# test.net
KiCad netlist of a schematic drawn in EAGLE
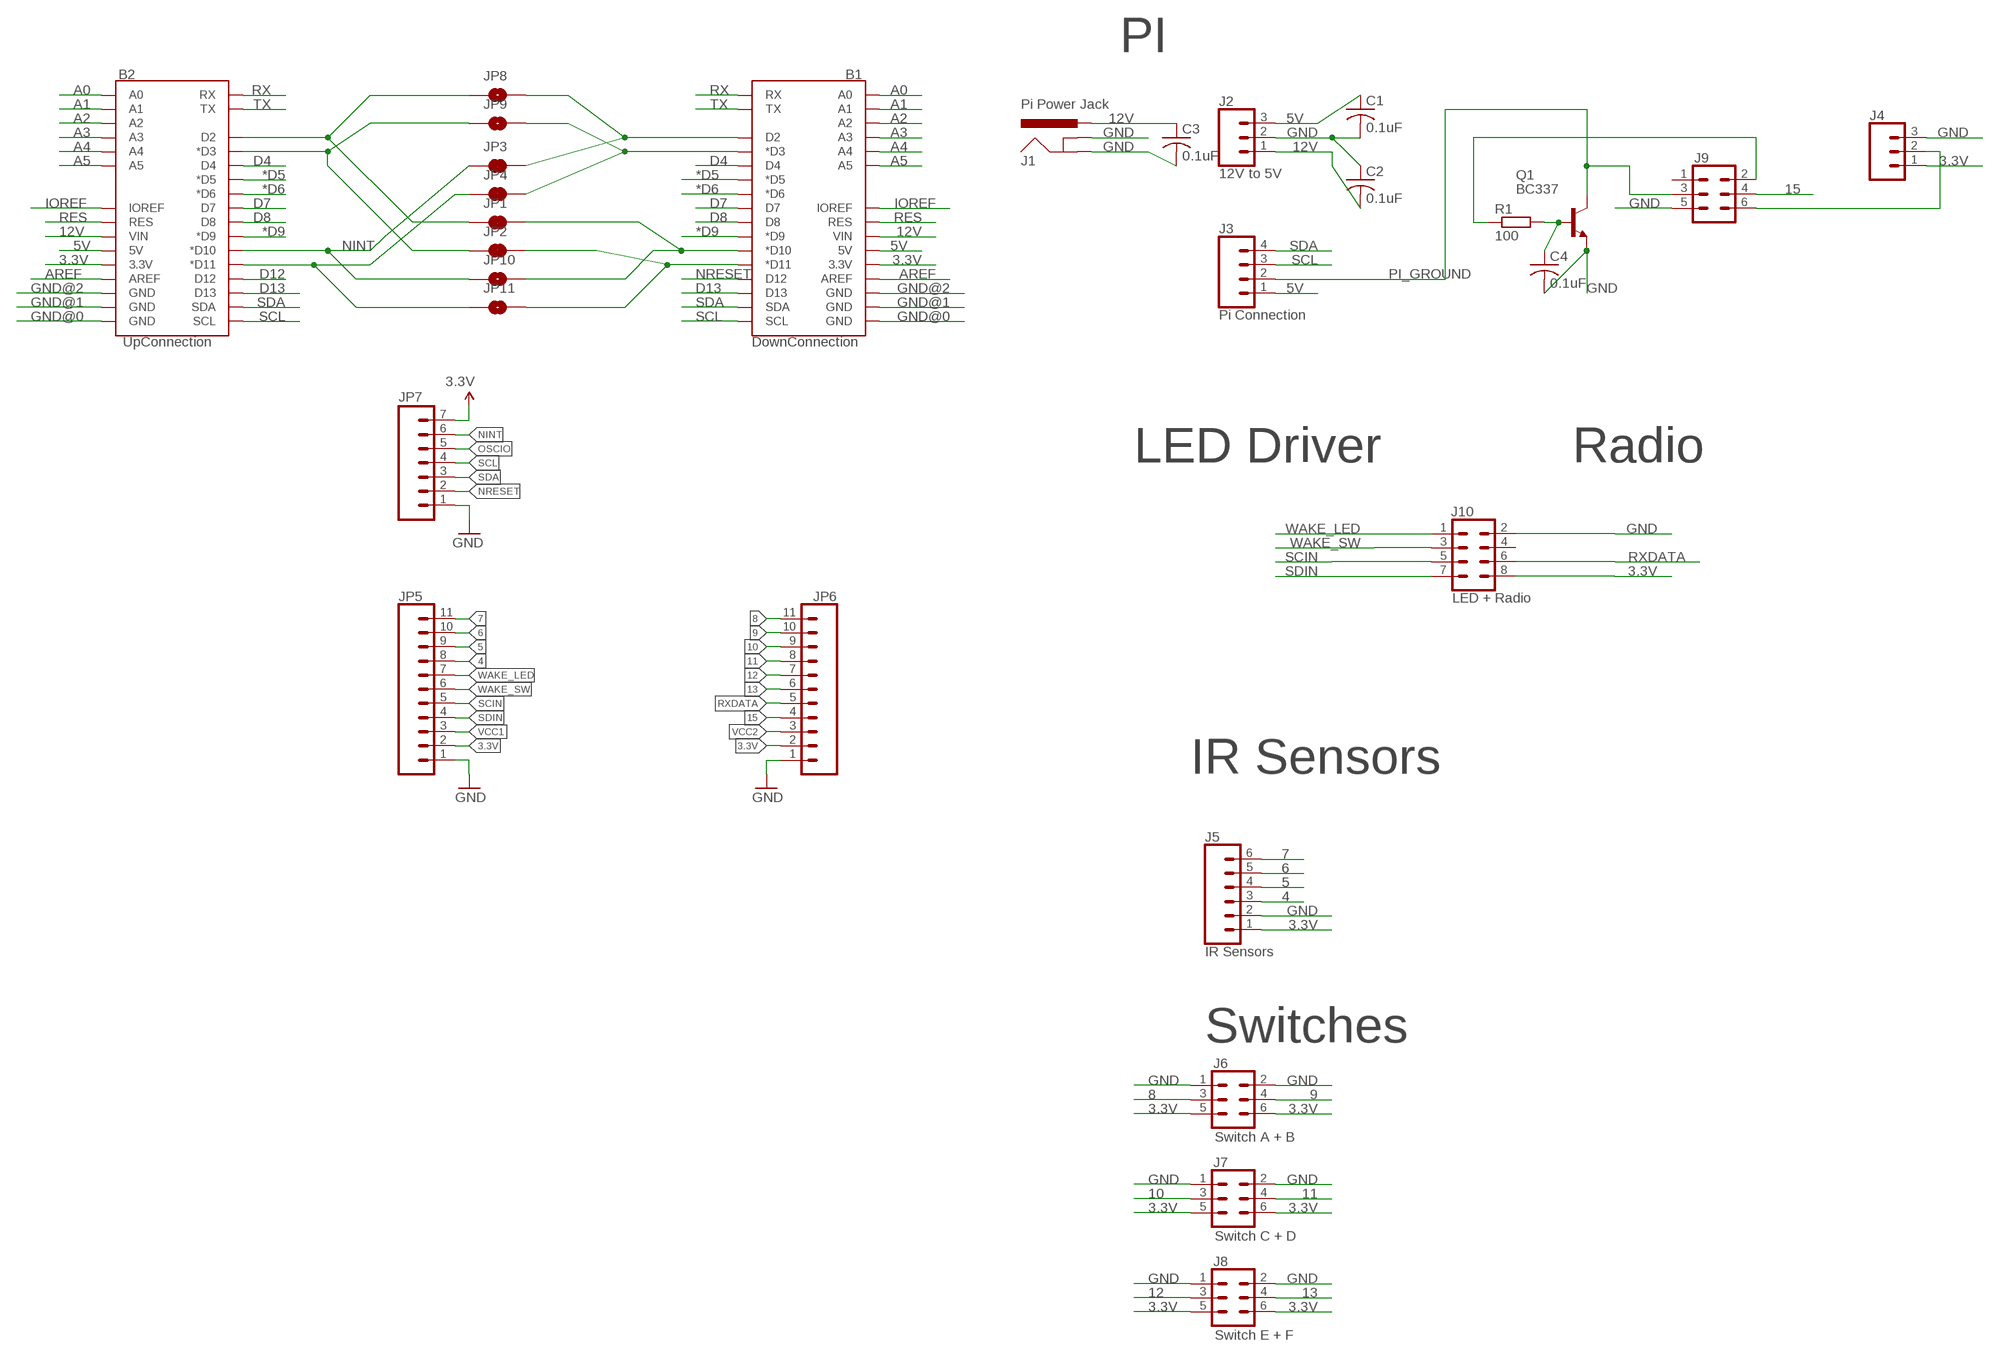
[diagram p0: schematic, sheet 1]

(export (version "E")
  (design (tool "Eeschema 10.0.6"))
  (components
    (comp (ref "B1")
      (value "DownConnection")
      (footprint "eagle-import:UNO_R3_SHIELD_NOLABELS")
      (libsource (lib "eagle-import") (part "ARDUINO_UNO_R3_SHIELDNOLABELS"))
    )
    (comp (ref "B2")
      (value "UpConnection")
      (footprint "eagle-import:UNO_R3_SHIELD_NOLABELS")
      (libsource (lib "eagle-import") (part "ARDUINO_UNO_R3_SHIELDNOLABELS"))
    )
    (comp (ref "C1")
      (value "0.1uF")
      (footprint "eagle-import:C025-024X044")
      (libsource (lib "eagle-import") (part "C-US025-024X044"))
    )
    (comp (ref "C2")
      (value "0.1uF")
      (footprint "eagle-import:C025-024X044")
      (libsource (lib "eagle-import") (part "C-US025-024X044"))
    )
    (comp (ref "C3")
      (value "0.1uF")
      (footprint "eagle-import:C025-024X044")
      (libsource (lib "eagle-import") (part "C-US025-024X044"))
    )
    (comp (ref "C4")
      (value "0.1uF")
      (footprint "eagle-import:C025-024X044")
      (libsource (lib "eagle-import") (part "C-US025-024X044"))
    )
    (comp (ref "J1")
      (value "Pi Power Jack")
      (footprint "eagle-import:POWER_JACK_PTH_BREAD")
      (libsource (lib "eagle-import") (part "POWER_JACKPTH_BREAD"))
    )
    (comp (ref "J2")
      (value "12V to 5V")
      (footprint "eagle-import:1X03")
      (libsource (lib "eagle-import") (part "CONN_03"))
    )
    (comp (ref "J3")
      (value "Pi Connection")
      (footprint "eagle-import:1X04")
      (libsource (lib "eagle-import") (part "CONN_04"))
    )
    (comp (ref "J4")
      (value "CONN_03")
      (footprint "eagle-import:1X03")
      (libsource (lib "eagle-import") (part "CONN_03"))
    )
    (comp (ref "J5")
      (value "IR Sensors")
      (footprint "eagle-import:1X06")
      (libsource (lib "eagle-import") (part "CONN_06SILK_FEMALE_PTH"))
    )
    (comp (ref "J6")
      (value "Switch A + B")
      (footprint "eagle-import:2X3")
      (libsource (lib "eagle-import") (part "CONN_03X2FEMALE"))
    )
    (comp (ref "J7")
      (value "Switch C + D")
      (footprint "eagle-import:2X3")
      (libsource (lib "eagle-import") (part "CONN_03X2FEMALE"))
    )
    (comp (ref "J8")
      (value "Switch E + F")
      (footprint "eagle-import:2X3")
      (libsource (lib "eagle-import") (part "CONN_03X2FEMALE"))
    )
    (comp (ref "J9")
      (value "CONN_03X2NO_SILK")
      (footprint "eagle-import:2X3-NS")
      (libsource (lib "eagle-import") (part "CONN_03X2NO_SILK"))
    )
    (comp (ref "J10")
      (value "LED + Radio")
      (footprint "eagle-import:2X4")
      (libsource (lib "eagle-import") (part "CONN_04X2"))
    )
    (comp (ref "JP1")
      (value "JUMPER-SMT_2_NC_TRACE_NO-SILK")
      (footprint "eagle-import:SMT-JUMPER_2_NC_TRACE_NO-SILK")
      (libsource (lib "eagle-import") (part "JUMPER-SMT_2_NC_TRACE_NO-SILK"))
    )
    (comp (ref "JP2")
      (value "JUMPER-SMT_2_NC_TRACE_NO-SILK")
      (footprint "eagle-import:SMT-JUMPER_2_NC_TRACE_NO-SILK")
      (libsource (lib "eagle-import") (part "JUMPER-SMT_2_NC_TRACE_NO-SILK"))
    )
    (comp (ref "JP3")
      (value "JUMPER-SMT_2_NC_TRACE_NO-SILK")
      (footprint "eagle-import:SMT-JUMPER_2_NC_TRACE_NO-SILK")
      (libsource (lib "eagle-import") (part "JUMPER-SMT_2_NC_TRACE_NO-SILK"))
    )
    (comp (ref "JP4")
      (value "JUMPER-SMT_2_NC_TRACE_NO-SILK")
      (footprint "eagle-import:SMT-JUMPER_2_NC_TRACE_NO-SILK")
      (libsource (lib "eagle-import") (part "JUMPER-SMT_2_NC_TRACE_NO-SILK"))
    )
    (comp (ref "JP5")
      (value "CONN_11")
      (footprint "eagle-import:1X11")
      (libsource (lib "eagle-import") (part "CONN_11"))
    )
    (comp (ref "JP6")
      (value "CONN_11")
      (footprint "eagle-import:1X11")
      (libsource (lib "eagle-import") (part "CONN_11"))
    )
    (comp (ref "JP7")
      (value "M07")
      (footprint "eagle-import:1X07")
      (libsource (lib "eagle-import") (part "M07"))
    )
    (comp (ref "JP8")
      (value "JUMPER-SMT_2_NO_NO-SILK")
      (footprint "eagle-import:SMT-JUMPER_2_NO_NO-SILK")
      (libsource (lib "eagle-import") (part "JUMPER-SMT_2_NO_NO-SILK"))
    )
    (comp (ref "JP9")
      (value "JUMPER-SMT_2_NO_NO-SILK")
      (footprint "eagle-import:SMT-JUMPER_2_NO_NO-SILK")
      (libsource (lib "eagle-import") (part "JUMPER-SMT_2_NO_NO-SILK"))
    )
    (comp (ref "JP10")
      (value "JUMPER-SMT_2_NO_NO-SILK")
      (footprint "eagle-import:SMT-JUMPER_2_NO_NO-SILK")
      (libsource (lib "eagle-import") (part "JUMPER-SMT_2_NO_NO-SILK"))
    )
    (comp (ref "JP11")
      (value "JUMPER-SMT_2_NO_NO-SILK")
      (footprint "eagle-import:SMT-JUMPER_2_NO_NO-SILK")
      (libsource (lib "eagle-import") (part "JUMPER-SMT_2_NO_NO-SILK"))
    )
    (comp (ref "Q1")
      (value "BC337")
      (footprint "eagle-import:TO92")
      (libsource (lib "eagle-import") (part "BC337"))
    )
    (comp (ref "R1")
      (value "100")
      (footprint "eagle-import:0204_7")
      (libsource (lib "eagle-import") (part "R0204/7"))
    )
  )
  (nets
    (net (code "1") (name "/*D5") (class "Default")
      (node (ref "B1") (pin "D5") (pinfunction "*D5_D5") (pintype "bidirectional"))
      (node (ref "B2") (pin "D5") (pinfunction "*D5_D5") (pintype "bidirectional"))
    )
    (net (code "2") (name "/*D6") (class "Default")
      (node (ref "B1") (pin "D6") (pinfunction "*D6_D6") (pintype "bidirectional"))
      (node (ref "B2") (pin "D6") (pinfunction "*D6_D6") (pintype "bidirectional"))
    )
    (net (code "3") (name "/*D9") (class "Default")
      (node (ref "B1") (pin "D9") (pinfunction "*D9_D9") (pintype "bidirectional"))
      (node (ref "B2") (pin "D9") (pinfunction "*D9_D9") (pintype "bidirectional"))
    )
    (net (code "4") (name "/5V") (class "Default")
      (node (ref "B1") (pin "5V") (pinfunction "5V_5V") (pintype "bidirectional"))
      (node (ref "B2") (pin "5V") (pinfunction "5V_5V") (pintype "bidirectional"))
      (node (ref "C1") (pin "1") (pinfunction "1_1") (pintype "passive"))
      (node (ref "J2") (pin "3") (pinfunction "3_3") (pintype "passive"))
      (node (ref "J3") (pin "1") (pinfunction "1_1") (pintype "passive"))
    )
    (net (code "5") (name "/12V") (class "Default")
      (node (ref "B1") (pin "VIN") (pinfunction "VIN_VIN") (pintype "bidirectional"))
      (node (ref "B2") (pin "VIN") (pinfunction "VIN_VIN") (pintype "bidirectional"))
      (node (ref "C2") (pin "2") (pinfunction "2_2") (pintype "passive"))
      (node (ref "C3") (pin "1") (pinfunction "1_1") (pintype "passive"))
      (node (ref "J1") (pin "PWR") (pinfunction "PWR_PWR") (pintype "bidirectional"))
      (node (ref "J2") (pin "1") (pinfunction "1_1") (pintype "passive"))
    )
    (net (code "6") (name "/A0") (class "Default")
      (node (ref "B1") (pin "A0") (pinfunction "A0_A0") (pintype "bidirectional"))
      (node (ref "B2") (pin "A0") (pinfunction "A0_A0") (pintype "bidirectional"))
    )
    (net (code "7") (name "/A1") (class "Default")
      (node (ref "B1") (pin "A1") (pinfunction "A1_A1") (pintype "bidirectional"))
      (node (ref "B2") (pin "A1") (pinfunction "A1_A1") (pintype "bidirectional"))
    )
    (net (code "8") (name "/A2") (class "Default")
      (node (ref "B1") (pin "A2") (pinfunction "A2_A2") (pintype "bidirectional"))
      (node (ref "B2") (pin "A2") (pinfunction "A2_A2") (pintype "bidirectional"))
    )
    (net (code "9") (name "/A3") (class "Default")
      (node (ref "B1") (pin "A3") (pinfunction "A3_A3") (pintype "bidirectional"))
      (node (ref "B2") (pin "A3") (pinfunction "A3_A3") (pintype "bidirectional"))
    )
    (net (code "10") (name "/A4") (class "Default")
      (node (ref "B1") (pin "A4") (pinfunction "A4_A4") (pintype "bidirectional"))
      (node (ref "B2") (pin "A4") (pinfunction "A4_A4") (pintype "bidirectional"))
    )
    (net (code "11") (name "/A5") (class "Default")
      (node (ref "B1") (pin "A5") (pinfunction "A5_A5") (pintype "bidirectional"))
      (node (ref "B2") (pin "A5") (pinfunction "A5_A5") (pintype "bidirectional"))
    )
    (net (code "12") (name "/AREF") (class "Default")
      (node (ref "B1") (pin "AREF") (pinfunction "AREF_AREF") (pintype "bidirectional"))
      (node (ref "B2") (pin "AREF") (pinfunction "AREF_AREF") (pintype "bidirectional"))
    )
    (net (code "13") (name "/D4") (class "Default")
      (node (ref "B1") (pin "D4") (pinfunction "D4_D4") (pintype "bidirectional"))
      (node (ref "B2") (pin "D4") (pinfunction "D4_D4") (pintype "bidirectional"))
    )
    (net (code "14") (name "/D7") (class "Default")
      (node (ref "B1") (pin "D7") (pinfunction "D7_D7") (pintype "bidirectional"))
      (node (ref "B2") (pin "D7") (pinfunction "D7_D7") (pintype "bidirectional"))
    )
    (net (code "15") (name "/D8") (class "Default")
      (node (ref "B1") (pin "D8") (pinfunction "D8_D8") (pintype "bidirectional"))
      (node (ref "B2") (pin "D8") (pinfunction "D8_D8") (pintype "bidirectional"))
    )
    (net (code "16") (name "/D12") (class "Default")
      (node (ref "B2") (pin "D12") (pinfunction "D12_D12") (pintype "bidirectional"))
    )
    (net (code "17") (name "/D13") (class "Default")
      (node (ref "B1") (pin "D13") (pinfunction "D13_D13") (pintype "bidirectional"))
      (node (ref "B2") (pin "D13") (pinfunction "D13_D13") (pintype "bidirectional"))
    )
    (net (code "18") (name "/GND@0") (class "Default")
      (node (ref "B1") (pin "GND@0") (pinfunction "GND_GND@0") (pintype "bidirectional"))
      (node (ref "B2") (pin "GND@0") (pinfunction "GND_GND@0") (pintype "bidirectional"))
    )
    (net (code "19") (name "/GND@1") (class "Default")
      (node (ref "B1") (pin "GND@1") (pinfunction "GND_GND@1") (pintype "bidirectional"))
      (node (ref "B2") (pin "GND@1") (pinfunction "GND_GND@1") (pintype "bidirectional"))
    )
    (net (code "20") (name "/GND@2") (class "Default")
      (node (ref "B1") (pin "GND@2") (pinfunction "GND_GND@2") (pintype "bidirectional"))
      (node (ref "B2") (pin "GND@2") (pinfunction "GND_GND@2") (pintype "bidirectional"))
    )
    (net (code "21") (name "/IOREF") (class "Default")
      (node (ref "B1") (pin "IOREF") (pinfunction "IOREF_IOREF") (pintype "bidirectional"))
      (node (ref "B2") (pin "IOREF") (pinfunction "IOREF_IOREF") (pintype "bidirectional"))
    )
    (net (code "22") (name "/PI_GROUND") (class "Default")
      (node (ref "J3") (pin "2") (pinfunction "2_2") (pintype "passive"))
      (node (ref "J9") (pin "3") (pinfunction "3_3") (pintype "bidirectional"))
      (node (ref "Q1") (pin "3") (pinfunction "C_3") (pintype "passive"))
    )
    (net (code "23") (name "/RES") (class "Default")
      (node (ref "B1") (pin "RES") (pinfunction "RES_RES") (pintype "bidirectional"))
      (node (ref "B2") (pin "RES") (pinfunction "RES_RES") (pintype "bidirectional"))
    )
    (net (code "24") (name "/RX") (class "Default")
      (node (ref "B1") (pin "RX") (pinfunction "RX_RX") (pintype "bidirectional"))
      (node (ref "B2") (pin "RX") (pinfunction "RX_RX") (pintype "bidirectional"))
    )
    (net (code "25") (name "/TX") (class "Default")
      (node (ref "B1") (pin "TX") (pinfunction "TX_TX") (pintype "bidirectional"))
      (node (ref "B2") (pin "TX") (pinfunction "TX_TX") (pintype "bidirectional"))
    )
    (net (code "26") (name "3.3V") (class "Default")
      (node (ref "B1") (pin "3.3V") (pinfunction "3.3V_3.3V") (pintype "bidirectional"))
      (node (ref "B2") (pin "3.3V") (pinfunction "3.3V_3.3V") (pintype "bidirectional"))
      (node (ref "J10") (pin "8") (pinfunction "8_8") (pintype "passive"))
      (node (ref "J4") (pin "1") (pinfunction "1_1") (pintype "passive"))
      (node (ref "J5") (pin "1") (pinfunction "1_1") (pintype "passive"))
      (node (ref "J6") (pin "5") (pinfunction "5_5") (pintype "bidirectional"))
      (node (ref "J6") (pin "6") (pinfunction "6_6") (pintype "bidirectional"))
      (node (ref "J7") (pin "5") (pinfunction "5_5") (pintype "bidirectional"))
      (node (ref "J7") (pin "6") (pinfunction "6_6") (pintype "bidirectional"))
      (node (ref "J8") (pin "5") (pinfunction "5_5") (pintype "bidirectional"))
      (node (ref "J8") (pin "6") (pinfunction "6_6") (pintype "bidirectional"))
      (node (ref "JP5") (pin "2") (pinfunction "2_2") (pintype "passive"))
      (node (ref "JP6") (pin "2") (pinfunction "2_2") (pintype "passive"))
      (node (ref "JP7") (pin "7") (pinfunction "7_7") (pintype "passive"))
    )
    (net (code "27") (name "4") (class "Default")
      (node (ref "J5") (pin "3") (pinfunction "3_3") (pintype "passive"))
      (node (ref "JP5") (pin "8") (pinfunction "8_8") (pintype "passive"))
    )
    (net (code "28") (name "5") (class "Default")
      (node (ref "J5") (pin "4") (pinfunction "4_4") (pintype "passive"))
      (node (ref "JP5") (pin "9") (pinfunction "9_9") (pintype "passive"))
    )
    (net (code "29") (name "6") (class "Default")
      (node (ref "J5") (pin "5") (pinfunction "5_5") (pintype "passive"))
      (node (ref "JP5") (pin "10") (pinfunction "10_10") (pintype "passive"))
    )
    (net (code "30") (name "7") (class "Default")
      (node (ref "J5") (pin "6") (pinfunction "6_6") (pintype "passive"))
      (node (ref "JP5") (pin "11") (pinfunction "11_11") (pintype "passive"))
    )
    (net (code "31") (name "8") (class "Default")
      (node (ref "J6") (pin "3") (pinfunction "3_3") (pintype "bidirectional"))
      (node (ref "JP6") (pin "11") (pinfunction "11_11") (pintype "passive"))
    )
    (net (code "32") (name "9") (class "Default")
      (node (ref "J6") (pin "4") (pinfunction "4_4") (pintype "bidirectional"))
      (node (ref "JP6") (pin "10") (pinfunction "10_10") (pintype "passive"))
    )
    (net (code "33") (name "10") (class "Default")
      (node (ref "J7") (pin "3") (pinfunction "3_3") (pintype "bidirectional"))
      (node (ref "JP6") (pin "9") (pinfunction "9_9") (pintype "passive"))
    )
    (net (code "34") (name "11") (class "Default")
      (node (ref "J7") (pin "4") (pinfunction "4_4") (pintype "bidirectional"))
      (node (ref "JP6") (pin "8") (pinfunction "8_8") (pintype "passive"))
    )
    (net (code "35") (name "12") (class "Default")
      (node (ref "J8") (pin "3") (pinfunction "3_3") (pintype "bidirectional"))
      (node (ref "JP6") (pin "7") (pinfunction "7_7") (pintype "passive"))
    )
    (net (code "36") (name "13") (class "Default")
      (node (ref "J8") (pin "4") (pinfunction "4_4") (pintype "bidirectional"))
      (node (ref "JP6") (pin "6") (pinfunction "6_6") (pintype "passive"))
    )
    (net (code "37") (name "15") (class "Default")
      (node (ref "J9") (pin "4") (pinfunction "4_4") (pintype "bidirectional"))
      (node (ref "JP6") (pin "4") (pinfunction "4_4") (pintype "passive"))
    )
    (net (code "38") (name "GND") (class "Default")
      (node (ref "C1") (pin "2") (pinfunction "2_2") (pintype "passive"))
      (node (ref "C2") (pin "1") (pinfunction "1_1") (pintype "passive"))
      (node (ref "C3") (pin "2") (pinfunction "2_2") (pintype "passive"))
      (node (ref "C4") (pin "2") (pinfunction "2_2") (pintype "passive"))
      (node (ref "J1") (pin "GND") (pinfunction "GND_GND") (pintype "bidirectional"))
      (node (ref "J1") (pin "GNDBREAK") (pinfunction "GNDBREAK_GNDBREAK") (pintype "bidirectional"))
      (node (ref "J10") (pin "2") (pinfunction "2_2") (pintype "passive"))
      (node (ref "J2") (pin "2") (pinfunction "2_2") (pintype "passive"))
      (node (ref "J4") (pin "3") (pinfunction "3_3") (pintype "passive"))
      (node (ref "J5") (pin "2") (pinfunction "2_2") (pintype "passive"))
      (node (ref "J6") (pin "1") (pinfunction "1_1") (pintype "bidirectional"))
      (node (ref "J6") (pin "2") (pinfunction "2_2") (pintype "bidirectional"))
      (node (ref "J7") (pin "1") (pinfunction "1_1") (pintype "bidirectional"))
      (node (ref "J7") (pin "2") (pinfunction "2_2") (pintype "bidirectional"))
      (node (ref "J8") (pin "1") (pinfunction "1_1") (pintype "bidirectional"))
      (node (ref "J8") (pin "2") (pinfunction "2_2") (pintype "bidirectional"))
      (node (ref "J9") (pin "5") (pinfunction "5_5") (pintype "bidirectional"))
      (node (ref "JP5") (pin "1") (pinfunction "1_1") (pintype "passive"))
      (node (ref "JP6") (pin "1") (pinfunction "1_1") (pintype "passive"))
      (node (ref "JP7") (pin "1") (pinfunction "1_1") (pintype "passive"))
      (node (ref "Q1") (pin "1") (pinfunction "E_1") (pintype "passive"))
    )
    (net (code "39") (name "NINT") (class "Default")
      (node (ref "B2") (pin "D10") (pinfunction "*D10_D10") (pintype "bidirectional"))
      (node (ref "JP10") (pin "1") (pinfunction "1_1") (pintype "passive"))
      (node (ref "JP3") (pin "1") (pinfunction "1_1") (pintype "passive"))
      (node (ref "JP7") (pin "6") (pinfunction "6_6") (pintype "passive"))
    )
    (net (code "40") (name "NRESET") (class "Default")
      (node (ref "B1") (pin "D12") (pinfunction "D12_D12") (pintype "bidirectional"))
      (node (ref "JP7") (pin "2") (pinfunction "2_2") (pintype "passive"))
    )
    (net (code "41") (name "Net-(B1-*D3)") (class "Default")
      (node (ref "B1") (pin "D3") (pinfunction "*D3_D3") (pintype "bidirectional"))
      (node (ref "JP4") (pin "2") (pinfunction "2_2") (pintype "passive"))
      (node (ref "JP9") (pin "2") (pinfunction "2_2") (pintype "passive"))
    )
    (net (code "42") (name "Net-(B1-*D10)") (class "Default")
      (node (ref "B1") (pin "D10") (pinfunction "*D10_D10") (pintype "bidirectional"))
      (node (ref "JP1") (pin "2") (pinfunction "2_2") (pintype "passive"))
      (node (ref "JP10") (pin "2") (pinfunction "2_2") (pintype "passive"))
    )
    (net (code "43") (name "Net-(B1-*D11)") (class "Default")
      (node (ref "B1") (pin "D11") (pinfunction "*D11_D11") (pintype "bidirectional"))
      (node (ref "JP11") (pin "2") (pinfunction "2_2") (pintype "passive"))
      (node (ref "JP2") (pin "2") (pinfunction "2_2") (pintype "passive"))
    )
    (net (code "44") (name "Net-(B1-PadD2)") (class "Default")
      (node (ref "B1") (pin "D2") (pinfunction "D2_D2") (pintype "bidirectional"))
      (node (ref "JP3") (pin "2") (pinfunction "2_2") (pintype "passive"))
      (node (ref "JP8") (pin "2") (pinfunction "2_2") (pintype "passive"))
    )
    (net (code "45") (name "Net-(B2-*D3)") (class "Default")
      (node (ref "B2") (pin "D3") (pinfunction "*D3_D3") (pintype "bidirectional"))
      (node (ref "JP2") (pin "1") (pinfunction "1_1") (pintype "passive"))
      (node (ref "JP9") (pin "1") (pinfunction "1_1") (pintype "passive"))
    )
    (net (code "46") (name "Net-(B2-*D11)") (class "Default")
      (node (ref "B2") (pin "D11") (pinfunction "*D11_D11") (pintype "bidirectional"))
      (node (ref "JP11") (pin "1") (pinfunction "1_1") (pintype "passive"))
      (node (ref "JP4") (pin "1") (pinfunction "1_1") (pintype "passive"))
    )
    (net (code "47") (name "Net-(B2-PadD2)") (class "Default")
      (node (ref "B2") (pin "D2") (pinfunction "D2_D2") (pintype "bidirectional"))
      (node (ref "JP1") (pin "1") (pinfunction "1_1") (pintype "passive"))
      (node (ref "JP8") (pin "1") (pinfunction "1_1") (pintype "passive"))
    )
    (net (code "48") (name "Net-(J4-Pad2)") (class "Default")
      (node (ref "J4") (pin "2") (pinfunction "2_2") (pintype "passive"))
      (node (ref "J9") (pin "6") (pinfunction "6_6") (pintype "bidirectional"))
    )
    (net (code "49") (name "Net-(J9-Pad2)") (class "Default")
      (node (ref "J9") (pin "2") (pinfunction "2_2") (pintype "bidirectional"))
      (node (ref "R1") (pin "1") (pinfunction "1_1") (pintype "passive"))
    )
    (net (code "50") (name "Net-(Q1-B)") (class "Default")
      (node (ref "C4") (pin "1") (pinfunction "1_1") (pintype "passive"))
      (node (ref "Q1") (pin "2") (pinfunction "B_2") (pintype "passive"))
      (node (ref "R1") (pin "2") (pinfunction "2_2") (pintype "passive"))
    )
    (net (code "51") (name "OSCIO") (class "Default")
      (node (ref "JP7") (pin "5") (pinfunction "5_5") (pintype "passive"))
    )
    (net (code "52") (name "RXDATA") (class "Default")
      (node (ref "J10") (pin "6") (pinfunction "6_6") (pintype "passive"))
      (node (ref "JP6") (pin "5") (pinfunction "5_5") (pintype "passive"))
    )
    (net (code "53") (name "SCIN") (class "Default")
      (node (ref "J10") (pin "5") (pinfunction "5_5") (pintype "passive"))
      (node (ref "JP5") (pin "5") (pinfunction "5_5") (pintype "passive"))
    )
    (net (code "54") (name "SCL") (class "Default")
      (node (ref "B1") (pin "SCL") (pinfunction "SCL_SCL") (pintype "bidirectional"))
      (node (ref "B2") (pin "SCL") (pinfunction "SCL_SCL") (pintype "bidirectional"))
      (node (ref "J3") (pin "3") (pinfunction "3_3") (pintype "passive"))
      (node (ref "JP7") (pin "4") (pinfunction "4_4") (pintype "passive"))
    )
    (net (code "55") (name "SDA") (class "Default")
      (node (ref "B1") (pin "SDA") (pinfunction "SDA_SDA") (pintype "bidirectional"))
      (node (ref "B2") (pin "SDA") (pinfunction "SDA_SDA") (pintype "bidirectional"))
      (node (ref "J3") (pin "4") (pinfunction "4_4") (pintype "passive"))
      (node (ref "JP7") (pin "3") (pinfunction "3_3") (pintype "passive"))
    )
    (net (code "56") (name "SDIN") (class "Default")
      (node (ref "J10") (pin "7") (pinfunction "7_7") (pintype "passive"))
      (node (ref "JP5") (pin "4") (pinfunction "4_4") (pintype "passive"))
    )
    (net (code "57") (name "VCC1") (class "Default")
      (node (ref "JP5") (pin "3") (pinfunction "3_3") (pintype "passive"))
    )
    (net (code "58") (name "VCC2") (class "Default")
      (node (ref "JP6") (pin "3") (pinfunction "3_3") (pintype "passive"))
    )
    (net (code "59") (name "WAKE_LED") (class "Default")
      (node (ref "J10") (pin "1") (pinfunction "1_1") (pintype "passive"))
      (node (ref "JP5") (pin "7") (pinfunction "7_7") (pintype "passive"))
    )
    (net (code "60") (name "WAKE_SW") (class "Default")
      (node (ref "J10") (pin "3") (pinfunction "3_3") (pintype "passive"))
      (node (ref "JP5") (pin "6") (pinfunction "6_6") (pintype "passive"))
    )
    (net (code "61") (name "unconnected-(J9-Pad1)") (class "Default")
      (node (ref "J9") (pin "1") (pinfunction "1_1") (pintype "bidirectional"))
    )
    (net (code "62") (name "unconnected-(J10-Pad4)") (class "Default")
      (node (ref "J10") (pin "4") (pinfunction "4_4") (pintype "passive"))
    )
  )
)
